# DVT-PSU-LM5116-HT_2.net
KiCad netlist of a schematic drawn in Altium Designer
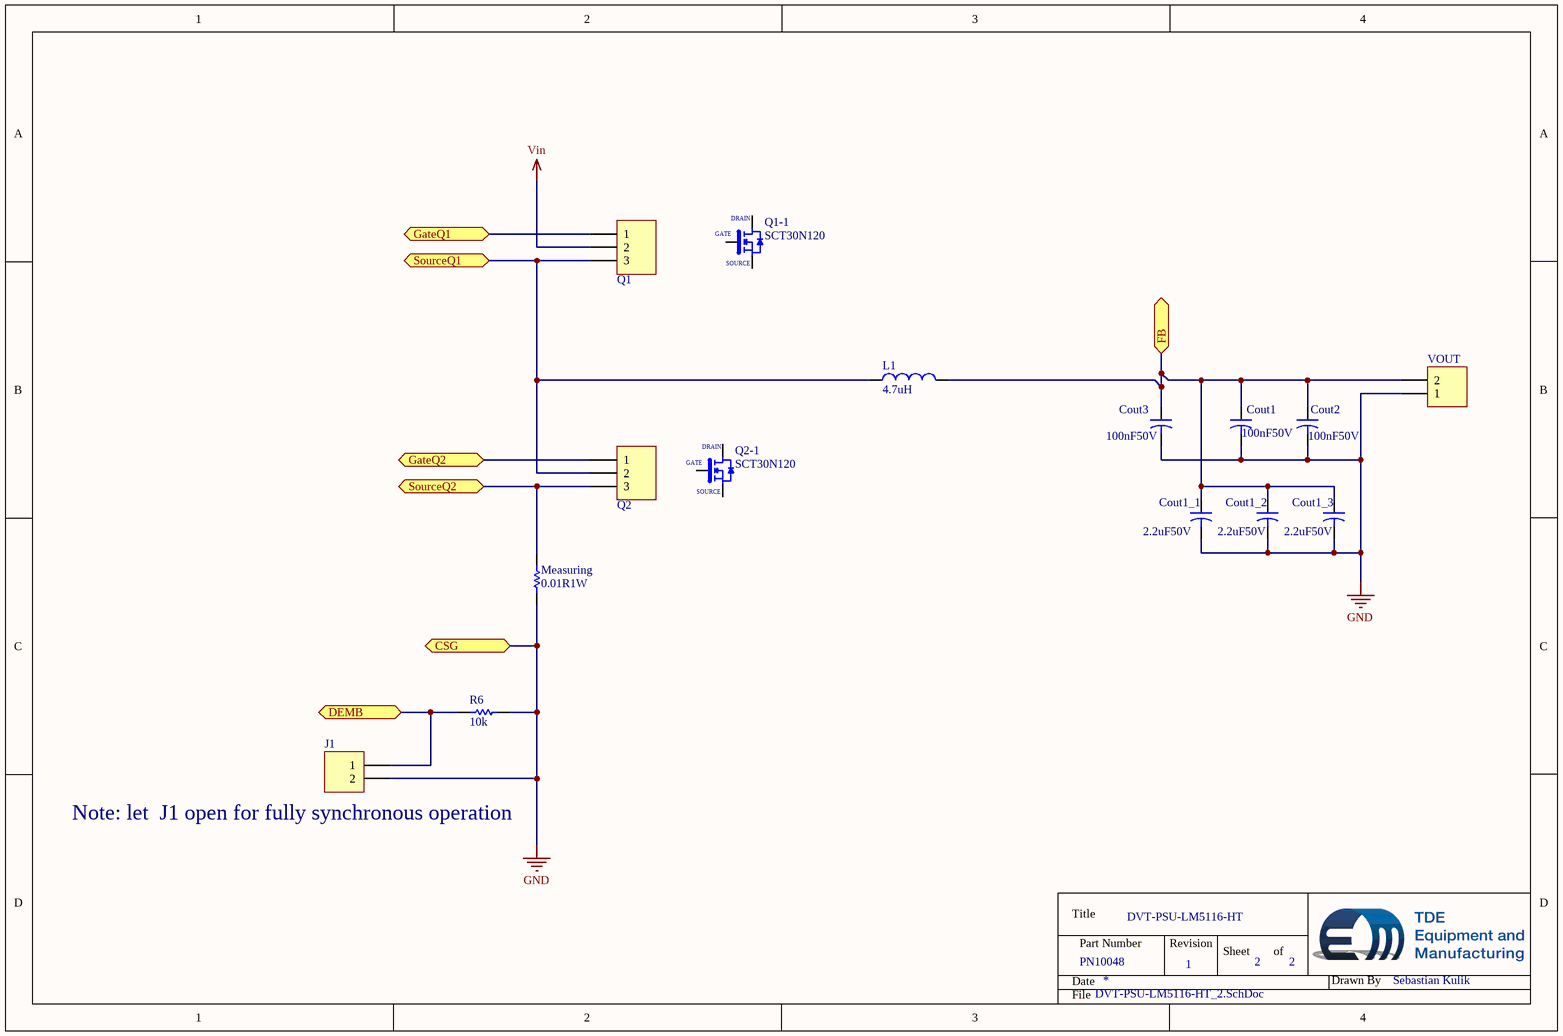
[diagram p0: DVT-PSU-LM5116-HT_2.SchDoc]

(export (version "E")
  (design (tool "Eeschema 10.0.6"))
  (components
    (comp (ref "**") (value "Eye") (footprint "Eye") (libsource (lib "ICs") (part "Eye")))
    (comp (ref "Cout1")
      (value "100nF50V")
      (footprint "Dummy-10mm")
      (description "Capacitor-Dummy-THT")
      (fields (field (name "PUBLISHER") "Sebastian Kulik"))
      (libsource (lib "Capacitors") (part "Capacitor-Dummy-THT"))
    )
    (comp (ref "Cout1_1")
      (value "2.2uF50V")
      (footprint "Dummy-10mm")
      (description "Capacitor-Dummy-THT")
      (fields (field (name "PUBLISHER") "Sebastian Kulik"))
      (libsource (lib "Capacitors") (part "Capacitor-Dummy-THT"))
    )
    (comp (ref "Cout1_2")
      (value "2.2uF50V")
      (footprint "Dummy-10mm")
      (description "Capacitor-Dummy-THT")
      (fields (field (name "PUBLISHER") "Sebastian Kulik"))
      (libsource (lib "Capacitors") (part "Capacitor-Dummy-THT"))
    )
    (comp (ref "Cout1_3")
      (value "2.2uF50V")
      (footprint "Dummy-10mm")
      (description "Capacitor-Dummy-THT")
      (fields (field (name "PUBLISHER") "Sebastian Kulik"))
      (libsource (lib "Capacitors") (part "Capacitor-Dummy-THT"))
    )
    (comp (ref "Cout2")
      (value "100nF50V")
      (footprint "Dummy-10mm")
      (description "Capacitor-Dummy-THT")
      (fields (field (name "PUBLISHER") "Sebastian Kulik"))
      (libsource (lib "Capacitors") (part "Capacitor-Dummy-THT"))
    )
    (comp (ref "Cout3")
      (value "100nF50V")
      (footprint "Dummy-10mm")
      (description "Capacitor-Dummy-THT")
      (fields (field (name "PUBLISHER") "Sebastian Kulik"))
      (libsource (lib "Capacitors") (part "Capacitor-Dummy-THT"))
    )
    (comp (ref "J1")
      (value "Plug_2_90_2.54")
      (footprint "HDR1X2")
      (description "Plug, 2-Pin")
      (fields (field (name "MANUFACTURER") "WE") (field (name "PUBLISHER") "Sebastian Kulik"))
      (libsource (lib "Connectors") (part "Plug_2_90_2.54"))
    )
    (comp (ref "L1")
      (value "4.7uH")
      (footprint "WE-LHMI1335")
      (description "WE, LHMI")
      (fields
        (field (name "MANUFACTURER") "WE")
        (field (name "Comment") "4u7H7.5A")
        (field (name "PUBLISHER") "Sebastian Kulik")
      )
      (libsource (lib "Passives") (part "4u7H7.5A"))
    )
    (comp (ref "Measuring")
      (value "0.01R1W")
      (footprint "Dummy-10mm")
      (description "LVR01, 0.01 ohm, 1 W, ± 1%")
      (fields
        (field (name "MANUFACTURER") "Vishay")
        (field (name "Comment") "Resistor-Dummy-THT")
        (field (name "PUBLISHER") "Sebastian Kulik")
      )
      (libsource (lib "Resistors") (part "Resistor-Dummy-THT"))
    )
    (comp (ref "Q1")
      (value "3Pol_TBL_5mm")
      (footprint "WE-TBL3-5")
      (description "Plug,-3-Pin")
      (fields (field (name "MANUFACTURER") "WE") (field (name "PUBLISHER") "Sebastian Kulik"))
      (libsource (lib "Connectors") (part "3Pol_TBL_5mm"))
    )
    (comp (ref "Q1-1") (value "SCT30N120") (libsource (lib "Discrete") (part "SCT30N120-Symbol")))
    (comp (ref "Q2")
      (value "3Pol_TBL_5mm")
      (footprint "WE-TBL3-5")
      (description "Plug,-3-Pin")
      (fields (field (name "MANUFACTURER") "WE") (field (name "PUBLISHER") "Sebastian Kulik"))
      (libsource (lib "Connectors") (part "3Pol_TBL_5mm"))
    )
    (comp (ref "Q2-1") (value "SCT30N120") (libsource (lib "Discrete") (part "SCT30N120-Symbol")))
    (comp (ref "R6")
      (value "10k")
      (footprint "Dummy-10mm")
      (description "Resistor-Dummy-THT")
      (fields (field (name "PUBLISHER") "Sebastian Kulik"))
      (libsource (lib "Resistors") (part "Resistor-Dummy-THT"))
    )
    (comp (ref "VOUT")
      (value "PHOENIX_1715721")
      (footprint "Phoenix-2-5_08")
      (description "Phoenix, 2 pol, 5.08mm, 22A, 715721")
      (fields (field (name "MANUFACTURER") "Phoenix") (field (name "PUBLISHER") "Sebastian Kulik"))
      (libsource (lib "Connectors") (part "2Pol_1715721"))
    )
  )
  (nets
    (net (code "1") (name "/DEMB") (class "Default")
      (node (ref "J1") (pin "1") (pinfunction "1_1") (pintype "passive"))
      (node (ref "R6") (pin "1") (pinfunction "1_1") (pintype "passive"))
    )
    (net (code "2") (name "/FB") (class "Default")
      (node (ref "Cout1") (pin "1") (pinfunction "1_1") (pintype "passive"))
      (node (ref "Cout1_1") (pin "1") (pinfunction "1_1") (pintype "passive"))
      (node (ref "Cout1_2") (pin "1") (pinfunction "1_1") (pintype "passive"))
      (node (ref "Cout1_3") (pin "1") (pinfunction "1_1") (pintype "passive"))
      (node (ref "Cout2") (pin "1") (pinfunction "1_1") (pintype "passive"))
      (node (ref "Cout3") (pin "1") (pinfunction "1_1") (pintype "passive"))
      (node (ref "L1") (pin "2") (pinfunction "2_2") (pintype "passive"))
      (node (ref "VOUT") (pin "2") (pinfunction "2_2") (pintype "passive"))
    )
    (net (code "3") (name "/GateQ1") (class "Default")
      (node (ref "Q1") (pin "1") (pinfunction "1_1") (pintype "passive"))
    )
    (net (code "4") (name "/GateQ2") (class "Default")
      (node (ref "Q2") (pin "1") (pinfunction "1_1") (pintype "passive"))
    )
    (net (code "5") (name "/SourceQ1") (class "Default")
      (node (ref "L1") (pin "1") (pinfunction "1_1") (pintype "passive"))
      (node (ref "Q1") (pin "3") (pinfunction "3_3") (pintype "passive"))
      (node (ref "Q2") (pin "2") (pinfunction "2_2") (pintype "passive"))
    )
    (net (code "6") (name "/SourceQ2") (class "Default")
      (node (ref "Measuring") (pin "2") (pinfunction "2_2") (pintype "passive"))
      (node (ref "Q2") (pin "3") (pinfunction "3_3") (pintype "passive"))
    )
    (net (code "7") (name "GND") (class "Default")
      (node (ref "Cout1") (pin "2") (pinfunction "2_2") (pintype "passive"))
      (node (ref "Cout1_1") (pin "2") (pinfunction "2_2") (pintype "passive"))
      (node (ref "Cout1_2") (pin "2") (pinfunction "2_2") (pintype "passive"))
      (node (ref "Cout1_3") (pin "2") (pinfunction "2_2") (pintype "passive"))
      (node (ref "Cout2") (pin "2") (pinfunction "2_2") (pintype "passive"))
      (node (ref "Cout3") (pin "2") (pinfunction "2_2") (pintype "passive"))
      (node (ref "J1") (pin "2") (pinfunction "2_2") (pintype "passive"))
      (node (ref "Measuring") (pin "1") (pinfunction "1_1") (pintype "passive"))
      (node (ref "R6") (pin "2") (pinfunction "2_2") (pintype "passive"))
      (node (ref "VOUT") (pin "1") (pinfunction "1_1") (pintype "passive"))
    )
    (net (code "8") (name "Vin") (class "Default")
      (node (ref "Q1") (pin "2") (pinfunction "2_2") (pintype "passive"))
    )
    (net (code "9") (name "unconnected-(Q1-1-Drain-Pad1)") (class "Default")
      (node (ref "Q1-1") (pin "1") (pinfunction "Drain_1") (pintype "passive"))
    )
    (net (code "10") (name "unconnected-(Q1-1-Gate-Pad3)") (class "Default")
      (node (ref "Q1-1") (pin "3") (pinfunction "Gate_3") (pintype "passive"))
    )
    (net (code "11") (name "unconnected-(Q1-1-Source-Pad2)") (class "Default")
      (node (ref "Q1-1") (pin "2") (pinfunction "Source_2") (pintype "passive"))
    )
    (net (code "12") (name "unconnected-(Q2-1-Drain-Pad1)") (class "Default")
      (node (ref "Q2-1") (pin "1") (pinfunction "Drain_1") (pintype "passive"))
    )
    (net (code "13") (name "unconnected-(Q2-1-Gate-Pad3)") (class "Default")
      (node (ref "Q2-1") (pin "3") (pinfunction "Gate_3") (pintype "passive"))
    )
    (net (code "14") (name "unconnected-(Q2-1-Source-Pad2)") (class "Default")
      (node (ref "Q2-1") (pin "2") (pinfunction "Source_2") (pintype "passive"))
    )
  )
)
